# DualDCMotor.net
KiCad netlist of a schematic drawn in EAGLE
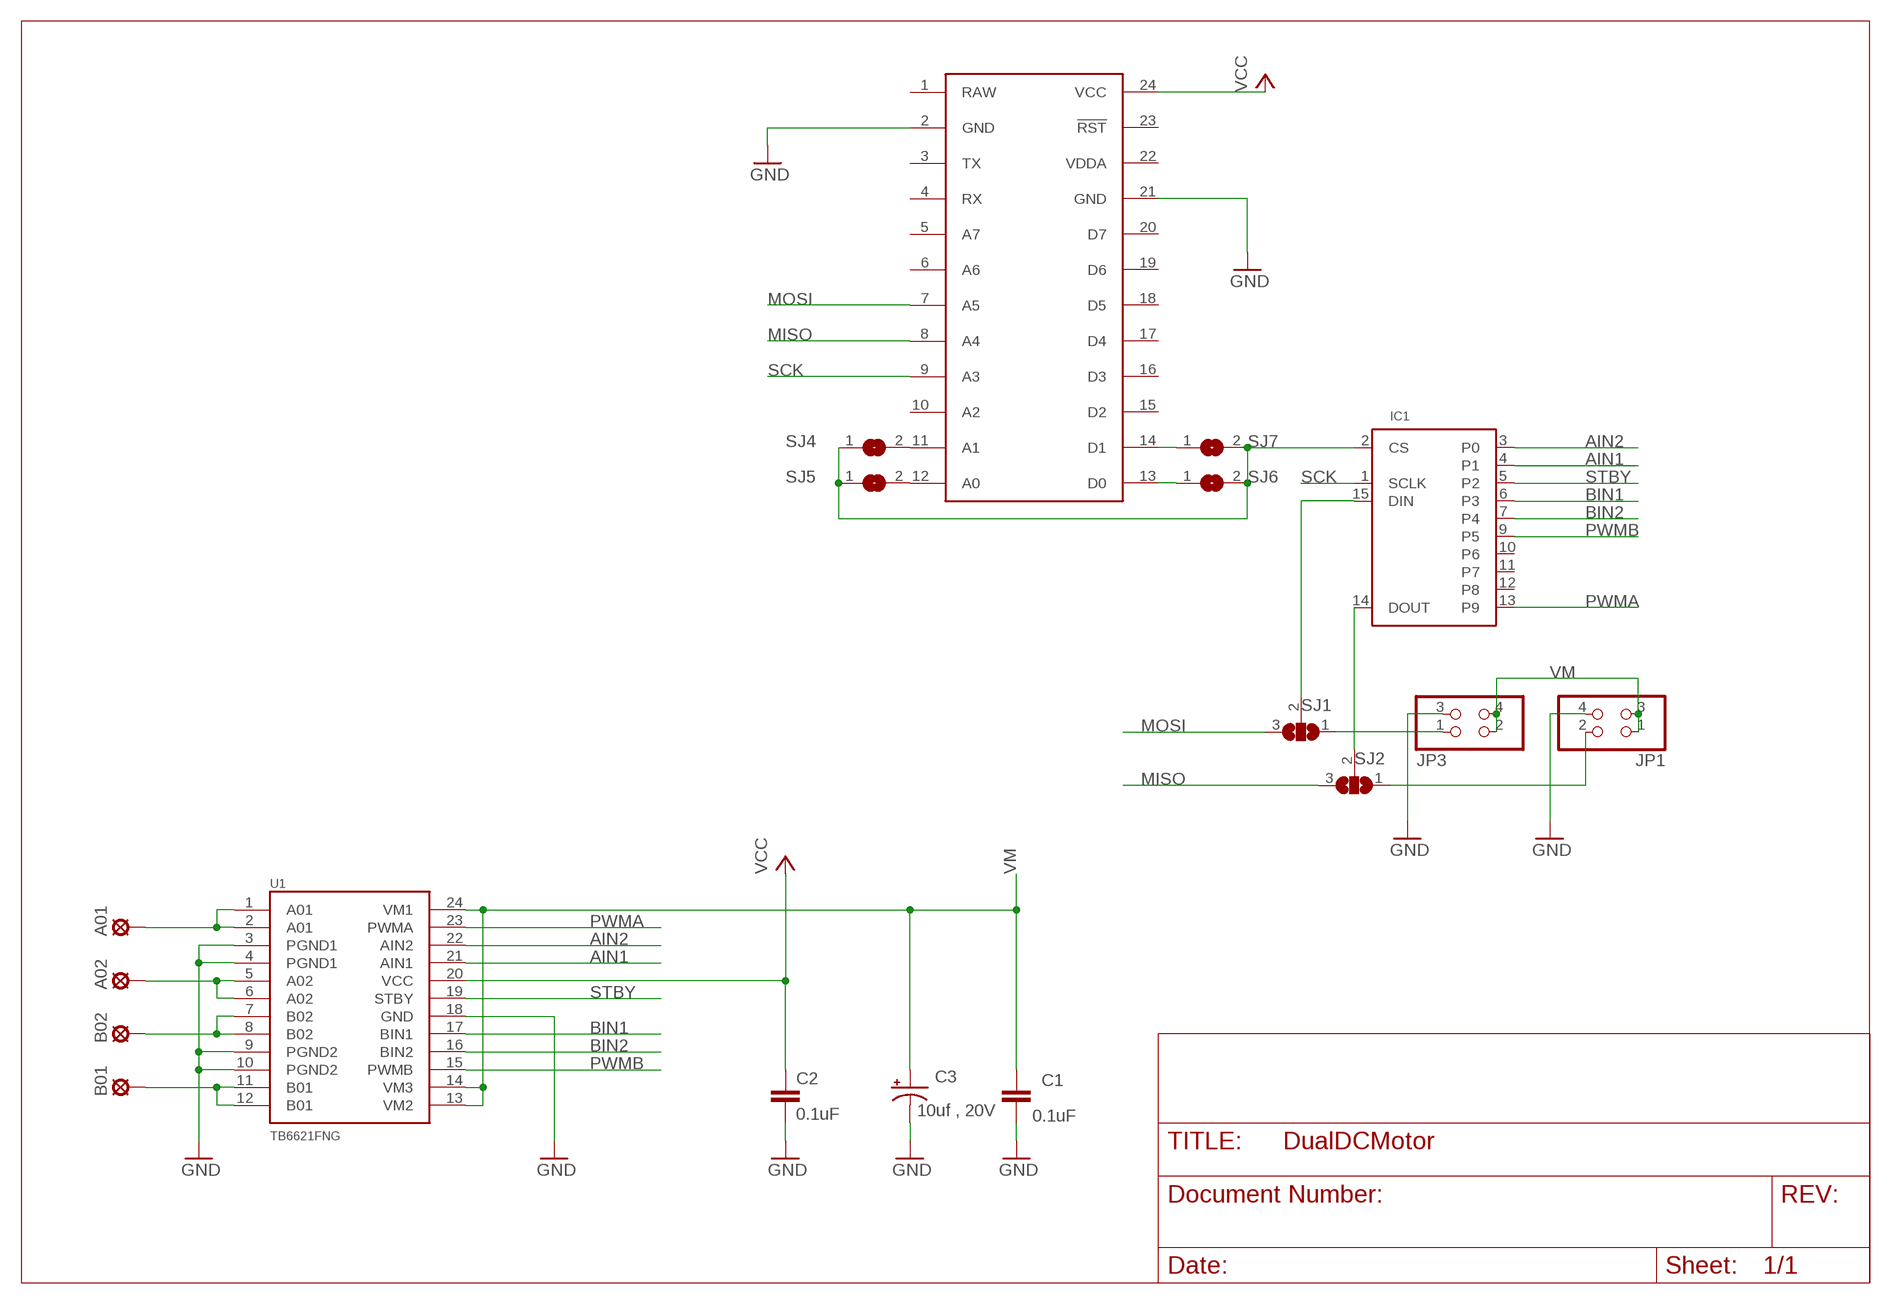
[diagram p0: schematic, sheet 1]

(export (version "E")
  (design (tool "Eeschema 10.0.6"))
  (components
    (comp (ref "A01")
      (value "LSP13")
      (footprint "eagle-import:LSP13")
      (libsource (lib "eagle-import") (part "LSP13"))
    )
    (comp (ref "A02")
      (value "LSP13")
      (footprint "eagle-import:LSP13")
      (libsource (lib "eagle-import") (part "LSP13"))
    )
    (comp (ref "B01")
      (value "LSP13")
      (footprint "eagle-import:LSP13")
      (libsource (lib "eagle-import") (part "LSP13"))
    )
    (comp (ref "B02")
      (value "LSP13")
      (footprint "eagle-import:LSP13")
      (libsource (lib "eagle-import") (part "LSP13"))
    )
    (comp (ref "C1")
      (value "0.1uF")
      (footprint "eagle-import:0402-CAP")
      (libsource (lib "eagle-import") (part "CAP0402-CAP"))
    )
    (comp (ref "C2")
      (value "0.1uF")
      (footprint "eagle-import:0402-CAP")
      (libsource (lib "eagle-import") (part "CAP0402-CAP"))
    )
    (comp (ref "C3")
      (value "10uf , 20V")
      (footprint "eagle-import:EIA3528")
      (libsource (lib "eagle-import") (part "CAP_POL3528"))
    )
    (comp (ref "IC1")
      (value "MAX6966AEE")
      (footprint "eagle-import:QSOP16")
      (libsource (lib "eagle-import") (part "MAX6966AEE"))
    )
    (comp (ref "JP1")
      (value "PINHD-2X02_2.54-SMD")
      (footprint "eagle-import:2X02SMD")
      (libsource (lib "eagle-import") (part "PINHD-2X02_2.54-SMD"))
    )
    (comp (ref "JP3")
      (value "PINHD-2X02_2.54-SMD")
      (footprint "eagle-import:2X02SMD")
      (libsource (lib "eagle-import") (part "PINHD-2X02_2.54-SMD"))
    )
    (comp (ref "SJ1")
      (value "SJ2W")
      (footprint "eagle-import:SJ_2")
      (libsource (lib "eagle-import") (part "SJ2W"))
    )
    (comp (ref "SJ2")
      (value "SJ2W")
      (footprint "eagle-import:SJ_2")
      (libsource (lib "eagle-import") (part "SJ2W"))
    )
    (comp (ref "SJ4") (value "SJ") (footprint "eagle-import:SJ") (libsource (lib "eagle-import") (part "SJ")))
    (comp (ref "SJ5") (value "SJ") (footprint "eagle-import:SJ") (libsource (lib "eagle-import") (part "SJ")))
    (comp (ref "SJ6") (value "SJ") (footprint "eagle-import:SJ") (libsource (lib "eagle-import") (part "SJ")))
    (comp (ref "SJ7") (value "SJ") (footprint "eagle-import:SJ") (libsource (lib "eagle-import") (part "SJ")))
    (comp (ref "U$1")
      (value "SPARK_CORECORE")
      (footprint "eagle-import:SPARK_CORE")
      (libsource (lib "eagle-import") (part "SPARK_CORECORE"))
    )
    (comp (ref "U1")
      (value "TB6621FNG")
      (footprint "eagle-import:SSOP24")
      (libsource (lib "eagle-import") (part "TB6621FNG"))
    )
  )
  (nets
    (net (code "1") (name "/AIN1") (class "Default")
      (node (ref "IC1") (pin "4") (pinfunction "P1_4") (pintype "output"))
      (node (ref "U1") (pin "21") (pinfunction "AIN1_21") (pintype "bidirectional"))
    )
    (net (code "2") (name "/AIN2") (class "Default")
      (node (ref "IC1") (pin "3") (pinfunction "P0_3") (pintype "output"))
      (node (ref "U1") (pin "22") (pinfunction "AIN2_22") (pintype "bidirectional"))
    )
    (net (code "3") (name "/BIN1") (class "Default")
      (node (ref "IC1") (pin "6") (pinfunction "P3_6") (pintype "output"))
      (node (ref "U1") (pin "17") (pinfunction "BIN1_17") (pintype "bidirectional"))
    )
    (net (code "4") (name "/BIN2") (class "Default")
      (node (ref "IC1") (pin "7") (pinfunction "P4_7") (pintype "output"))
      (node (ref "U1") (pin "16") (pinfunction "BIN2_16") (pintype "bidirectional"))
    )
    (net (code "5") (name "/MISO") (class "Default")
      (node (ref "SJ2") (pin "3") (pinfunction "3_3") (pintype "passive"))
      (node (ref "U$1") (pin "8") (pinfunction "A4_8") (pintype "bidirectional"))
    )
    (net (code "6") (name "/MOSI") (class "Default")
      (node (ref "SJ1") (pin "3") (pinfunction "3_3") (pintype "passive"))
      (node (ref "U$1") (pin "7") (pinfunction "A5_7") (pintype "bidirectional"))
    )
    (net (code "7") (name "/PWMA") (class "Default")
      (node (ref "IC1") (pin "13") (pinfunction "P9_13") (pintype "output"))
      (node (ref "U1") (pin "23") (pinfunction "PWMA_23") (pintype "bidirectional"))
    )
    (net (code "8") (name "/PWMB") (class "Default")
      (node (ref "IC1") (pin "9") (pinfunction "P5_9") (pintype "output"))
      (node (ref "U1") (pin "15") (pinfunction "PWMB_15") (pintype "bidirectional"))
    )
    (net (code "9") (name "/RAW") (class "Default")
      (node (ref "U$1") (pin "1") (pinfunction "RAW_1") (pintype "power_in"))
    )
    (net (code "10") (name "/SCK") (class "Default")
      (node (ref "IC1") (pin "1") (pinfunction "SCLK_1") (pintype "input"))
      (node (ref "U$1") (pin "9") (pinfunction "A3_9") (pintype "bidirectional"))
    )
    (net (code "11") (name "/STBY") (class "Default")
      (node (ref "IC1") (pin "5") (pinfunction "P2_5") (pintype "output"))
      (node (ref "U1") (pin "19") (pinfunction "STBY_19") (pintype "bidirectional"))
    )
    (net (code "12") (name "/VDDA") (class "Default")
      (node (ref "U$1") (pin "22") (pinfunction "VDDA_22") (pintype "power_in"))
    )
    (net (code "13") (name "/VM") (class "Default")
      (node (ref "C1") (pin "1") (pinfunction "1_1") (pintype "passive"))
      (node (ref "C3") (pin "A") (pinfunction "+_A") (pintype "passive"))
      (node (ref "JP1") (pin "1") (pinfunction "1_1") (pintype "passive"))
      (node (ref "JP1") (pin "3") (pinfunction "3_3") (pintype "passive"))
      (node (ref "JP3") (pin "2") (pinfunction "2_2") (pintype "passive"))
      (node (ref "JP3") (pin "4") (pinfunction "4_4") (pintype "passive"))
      (node (ref "U1") (pin "13") (pinfunction "VM2_13") (pintype "bidirectional"))
      (node (ref "U1") (pin "14") (pinfunction "VM3_14") (pintype "bidirectional"))
      (node (ref "U1") (pin "24") (pinfunction "VM1_24") (pintype "bidirectional"))
    )
    (net (code "14") (name "GND") (class "Default")
      (node (ref "C1") (pin "2") (pinfunction "2_2") (pintype "passive"))
      (node (ref "C2") (pin "2") (pinfunction "2_2") (pintype "passive"))
      (node (ref "C3") (pin "C") (pinfunction "-_C") (pintype "passive"))
      (node (ref "JP1") (pin "4") (pinfunction "4_4") (pintype "passive"))
      (node (ref "JP3") (pin "3") (pinfunction "3_3") (pintype "passive"))
      (node (ref "U$1") (pin "2") (pinfunction "GND_2") (pintype "power_in"))
      (node (ref "U$1") (pin "21") (pinfunction "GND_21") (pintype "power_in"))
      (node (ref "U1") (pin "10") (pinfunction "PGND2_10") (pintype "bidirectional"))
      (node (ref "U1") (pin "18") (pinfunction "GND_18") (pintype "bidirectional"))
      (node (ref "U1") (pin "3") (pinfunction "PGND1_3") (pintype "bidirectional"))
      (node (ref "U1") (pin "4") (pinfunction "PGND1_4") (pintype "bidirectional"))
      (node (ref "U1") (pin "9") (pinfunction "PGND2_9") (pintype "bidirectional"))
    )
    (net (code "15") (name "Net-(A01-PadMP)") (class "Default")
      (node (ref "A01") (pin "MP") (pinfunction "MP_MP") (pintype "passive"))
      (node (ref "U1") (pin "1") (pinfunction "A01_1") (pintype "bidirectional"))
      (node (ref "U1") (pin "2") (pinfunction "A01_2") (pintype "bidirectional"))
    )
    (net (code "16") (name "Net-(A02-PadMP)") (class "Default")
      (node (ref "A02") (pin "MP") (pinfunction "MP_MP") (pintype "passive"))
      (node (ref "U1") (pin "5") (pinfunction "A02_5") (pintype "bidirectional"))
      (node (ref "U1") (pin "6") (pinfunction "A02_6") (pintype "bidirectional"))
    )
    (net (code "17") (name "Net-(B01-PadMP)") (class "Default")
      (node (ref "B01") (pin "MP") (pinfunction "MP_MP") (pintype "passive"))
      (node (ref "U1") (pin "11") (pinfunction "B01_11") (pintype "bidirectional"))
      (node (ref "U1") (pin "12") (pinfunction "B01_12") (pintype "bidirectional"))
    )
    (net (code "18") (name "Net-(B02-PadMP)") (class "Default")
      (node (ref "B02") (pin "MP") (pinfunction "MP_MP") (pintype "passive"))
      (node (ref "U1") (pin "7") (pinfunction "B02_7") (pintype "bidirectional"))
      (node (ref "U1") (pin "8") (pinfunction "B02_8") (pintype "bidirectional"))
    )
    (net (code "19") (name "Net-(IC1A-CS)") (class "Default")
      (node (ref "IC1") (pin "2") (pinfunction "CS_2") (pintype "input"))
      (node (ref "SJ4") (pin "1") (pinfunction "1_1") (pintype "passive"))
      (node (ref "SJ5") (pin "1") (pinfunction "1_1") (pintype "passive"))
      (node (ref "SJ6") (pin "2") (pinfunction "2_2") (pintype "passive"))
      (node (ref "SJ7") (pin "2") (pinfunction "2_2") (pintype "passive"))
    )
    (net (code "20") (name "Net-(IC1A-DIN)") (class "Default")
      (node (ref "IC1") (pin "15") (pinfunction "DIN_15") (pintype "input"))
      (node (ref "SJ1") (pin "2") (pinfunction "2_2") (pintype "passive"))
    )
    (net (code "21") (name "Net-(IC1A-DOUT)") (class "Default")
      (node (ref "IC1") (pin "14") (pinfunction "DOUT_14") (pintype "output"))
      (node (ref "SJ2") (pin "2") (pinfunction "2_2") (pintype "passive"))
    )
    (net (code "22") (name "Net-(JP1-Pad2)") (class "Default")
      (node (ref "JP1") (pin "2") (pinfunction "2_2") (pintype "passive"))
      (node (ref "SJ2") (pin "1") (pinfunction "1_1") (pintype "passive"))
    )
    (net (code "23") (name "Net-(JP3-Pad1)") (class "Default")
      (node (ref "JP3") (pin "1") (pinfunction "1_1") (pintype "passive"))
      (node (ref "SJ1") (pin "1") (pinfunction "1_1") (pintype "passive"))
    )
    (net (code "24") (name "Net-(U$1-A0)") (class "Default")
      (node (ref "SJ5") (pin "2") (pinfunction "2_2") (pintype "passive"))
      (node (ref "U$1") (pin "12") (pinfunction "A0_12") (pintype "bidirectional"))
    )
    (net (code "25") (name "Net-(U$1-A1)") (class "Default")
      (node (ref "SJ4") (pin "2") (pinfunction "2_2") (pintype "passive"))
      (node (ref "U$1") (pin "11") (pinfunction "A1_11") (pintype "bidirectional"))
    )
    (net (code "26") (name "Net-(U$1-D0)") (class "Default")
      (node (ref "SJ6") (pin "1") (pinfunction "1_1") (pintype "passive"))
      (node (ref "U$1") (pin "13") (pinfunction "D0_13") (pintype "bidirectional"))
    )
    (net (code "27") (name "Net-(U$1-D1)") (class "Default")
      (node (ref "SJ7") (pin "1") (pinfunction "1_1") (pintype "passive"))
      (node (ref "U$1") (pin "14") (pinfunction "D1_14") (pintype "bidirectional"))
    )
    (net (code "28") (name "VCC") (class "Default")
      (node (ref "C2") (pin "1") (pinfunction "1_1") (pintype "passive"))
      (node (ref "U$1") (pin "24") (pinfunction "VCC_24") (pintype "power_in"))
      (node (ref "U1") (pin "20") (pinfunction "VCC_20") (pintype "bidirectional"))
    )
    (net (code "29") (name "unconnected-(IC1A-P6-Pad10)") (class "Default")
      (node (ref "IC1") (pin "10") (pinfunction "P6_10") (pintype "output"))
    )
    (net (code "30") (name "unconnected-(IC1A-P7-Pad11)") (class "Default")
      (node (ref "IC1") (pin "11") (pinfunction "P7_11") (pintype "output"))
    )
    (net (code "31") (name "unconnected-(IC1A-P8-Pad12)") (class "Default")
      (node (ref "IC1") (pin "12") (pinfunction "P8_12") (pintype "output"))
    )
    (net (code "32") (name "unconnected-(U$1-A2-Pad10)") (class "Default")
      (node (ref "U$1") (pin "10") (pinfunction "A2_10") (pintype "bidirectional"))
    )
    (net (code "33") (name "unconnected-(U$1-A6-Pad6)") (class "Default")
      (node (ref "U$1") (pin "6") (pinfunction "A6_6") (pintype "bidirectional"))
    )
    (net (code "34") (name "unconnected-(U$1-A7-Pad5)") (class "Default")
      (node (ref "U$1") (pin "5") (pinfunction "A7_5") (pintype "bidirectional"))
    )
    (net (code "35") (name "unconnected-(U$1-D2-Pad15)") (class "Default")
      (node (ref "U$1") (pin "15") (pinfunction "D2_15") (pintype "bidirectional"))
    )
    (net (code "36") (name "unconnected-(U$1-D3-Pad16)") (class "Default")
      (node (ref "U$1") (pin "16") (pinfunction "D3_16") (pintype "bidirectional"))
    )
    (net (code "37") (name "unconnected-(U$1-D4-Pad17)") (class "Default")
      (node (ref "U$1") (pin "17") (pinfunction "D4_17") (pintype "bidirectional"))
    )
    (net (code "38") (name "unconnected-(U$1-D5-Pad18)") (class "Default")
      (node (ref "U$1") (pin "18") (pinfunction "D5_18") (pintype "bidirectional"))
    )
    (net (code "39") (name "unconnected-(U$1-D6-Pad19)") (class "Default")
      (node (ref "U$1") (pin "19") (pinfunction "D6_19") (pintype "bidirectional"))
    )
    (net (code "40") (name "unconnected-(U$1-D7-Pad20)") (class "Default")
      (node (ref "U$1") (pin "20") (pinfunction "D7_20") (pintype "bidirectional"))
    )
    (net (code "41") (name "unconnected-(U$1-RX-Pad4)") (class "Default")
      (node (ref "U$1") (pin "4") (pinfunction "RX_4") (pintype "bidirectional"))
    )
    (net (code "42") (name "unconnected-(U$1-TX-Pad3)") (class "Default")
      (node (ref "U$1") (pin "3") (pinfunction "TX_3") (pintype "bidirectional"))
    )
    (net (code "43") (name "unconnected-(U$1-~{RST}-Pad23)") (class "Default")
      (node (ref "U$1") (pin "23") (pinfunction "~{RST}_23") (pintype "bidirectional"))
    )
  )
)
